# P_EV.net
KiCad netlist of a schematic drawn in Altium Designer
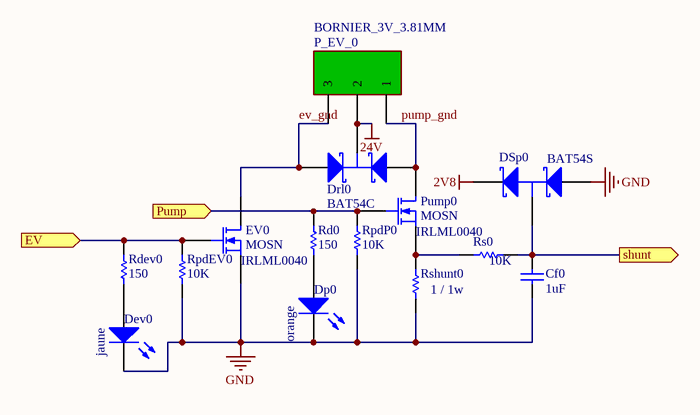
[diagram p0: P+EV.SchDoc]

(export (version "E")
  (design (tool "Eeschema 10.0.6"))
  (components
    (comp (ref "Cf0")
      (value "1uF")
      (footprint "C0805_N")
      (description "Capacitor")
      (fields (field (name "PUBLISHER") "Altium Limited"))
      (libsource (lib "_ROBOT") (part "Condensateur"))
    )
    (comp (ref "Dev0")
      (value "jaune")
      (footprint "LED_0805")
      (description "Typical LED")
      (fields (field (name "PUBLISHER") "Altium Limited"))
      (libsource (lib "_ROBOT") (part "LED"))
    )
    (comp (ref "Dp0")
      (value "orange")
      (footprint "LED_0805")
      (description "Typical LED")
      (fields (field (name "PUBLISHER") "Altium Limited"))
      (libsource (lib "_ROBOT") (part "LED"))
    )
    (comp (ref "Drl0")
      (value "BAT54C")
      (footprint "SOT23-3N")
      (description "DIODE SCHOTTKY DOUBLE")
      (fields (field (name "MANUFACTURER") "ZETEX"))
      (libsource (lib "_ROBOT") (part "Diode Shottky double BAT54C"))
    )
    (comp (ref "DSp0")
      (value "BAT54S")
      (footprint "SOT23-3N")
      (description "DIODE SCHOTTKY DOUBLE")
      (fields (field (name "MANUFACTURER") "ZETEX"))
      (libsource (lib "_ROBOT") (part "Diode Shottky double BAT54S"))
    )
    (comp (ref "EV0")
      (value "MOSN")
      (footprint "SOT23-3N")
      (description "N-Channel MOSFET")
      (fields (field (name "ALTIUM_UNNAMED_1") "IRLML0040") (field (name "PUBLISHER") "Altium Limited"))
      (libsource (lib "_ROBOT") (part "Transistor MOSFET-N"))
    )
    (comp (ref "Pump0")
      (value "MOSN")
      (footprint "SOT23-3N")
      (description "N-Channel MOSFET")
      (fields (field (name "ALTIUM_UNNAMED_1") "IRLML0040") (field (name "PUBLISHER") "Altium Limited"))
      (libsource (lib "_ROBOT") (part "Transistor MOSFET-N"))
    )
    (comp (ref "P_EV_0")
      (value "BORNIER_3V_3.81MM")
      (footprint "BORNIER_3V_3.81MM")
      (libsource (lib "Connecteur") (part "BORNIER_3V_3.81MM"))
    )
    (comp (ref "Rd0")
      (value "150")
      (footprint "R1206_N")
      (description "Resistor")
      (fields (field (name "PUBLISHER") "Altium Limited"))
      (libsource (lib "_ROBOT") (part "Resistor"))
    )
    (comp (ref "Rdev0")
      (value "150")
      (footprint "R1206_N")
      (description "Resistor")
      (fields (field (name "PUBLISHER") "Altium Limited"))
      (libsource (lib "_ROBOT") (part "Resistor"))
    )
    (comp (ref "RpdEV0")
      (value "10K")
      (footprint "R1206_N")
      (description "Resistor")
      (fields (field (name "PUBLISHER") "Altium Limited"))
      (libsource (lib "_ROBOT") (part "Resistor"))
    )
    (comp (ref "RpdP0")
      (value "10K")
      (footprint "R1206_N")
      (description "Resistor")
      (fields (field (name "PUBLISHER") "Altium Limited"))
      (libsource (lib "_ROBOT") (part "Resistor"))
    )
    (comp (ref "Rs0")
      (value "10K")
      (footprint "R1206_N")
      (description "Resistor")
      (fields (field (name "PUBLISHER") "Altium Limited"))
      (libsource (lib "_ROBOT") (part "Resistor"))
    )
    (comp (ref "Rshunt0")
      (value "1 / 1w")
      (footprint "INDUCTANCE_CMS_1812")
      (description "Resistor")
      (fields (field (name "PUBLISHER") "Altium Limited"))
      (libsource (lib "_ROBOT") (part "Resistor"))
    )
  )
  (nets
    (net (code "1") (name "/EV") (class "Default")
      (node (ref "EV0") (pin "1") (pinfunction "G_1") (pintype "passive"))
      (node (ref "Rdev0") (pin "2") (pinfunction "2_2") (pintype "passive"))
      (node (ref "RpdEV0") (pin "2") (pinfunction "2_2") (pintype "passive"))
    )
    (net (code "2") (name "/Pump") (class "Default")
      (node (ref "Pump0") (pin "1") (pinfunction "G_1") (pintype "passive"))
      (node (ref "Rd0") (pin "2") (pinfunction "2_2") (pintype "passive"))
      (node (ref "RpdP0") (pin "2") (pinfunction "2_2") (pintype "passive"))
    )
    (net (code "3") (name "/ev_gnd") (class "Default")
      (node (ref "Drl0") (pin "1") (pinfunction "A1_1") (pintype "passive"))
      (node (ref "EV0") (pin "3") (pinfunction "D_3") (pintype "passive"))
      (node (ref "P_EV_0") (pin "3") (pinfunction "3_3") (pintype "passive"))
    )
    (net (code "4") (name "/pump_gnd") (class "Default")
      (node (ref "Drl0") (pin "2") (pinfunction "A2_2") (pintype "passive"))
      (node (ref "P_EV_0") (pin "1") (pinfunction "1_1") (pintype "passive"))
      (node (ref "Pump0") (pin "3") (pinfunction "D_3") (pintype "passive"))
    )
    (net (code "5") (name "/shunt") (class "Default")
      (node (ref "Cf0") (pin "2") (pinfunction "2_2") (pintype "passive"))
      (node (ref "DSp0") (pin "3") (pinfunction "C_3") (pintype "passive"))
      (node (ref "Rs0") (pin "2") (pinfunction "2_2") (pintype "passive"))
    )
    (net (code "6") (name "2V8") (class "Default")
      (node (ref "DSp0") (pin "2") (pinfunction "K_2") (pintype "passive"))
    )
    (net (code "7") (name "24V") (class "Default")
      (node (ref "Drl0") (pin "3") (pinfunction "K_3") (pintype "passive"))
      (node (ref "P_EV_0") (pin "2") (pinfunction "2_2") (pintype "passive"))
    )
    (net (code "8") (name "GND") (class "Default")
      (node (ref "Cf0") (pin "1") (pinfunction "1_1") (pintype "passive"))
      (node (ref "DSp0") (pin "1") (pinfunction "A_1") (pintype "passive"))
      (node (ref "Dev0") (pin "2") (pinfunction "K_2") (pintype "passive"))
      (node (ref "Dp0") (pin "2") (pinfunction "K_2") (pintype "passive"))
      (node (ref "EV0") (pin "2") (pinfunction "S_2") (pintype "passive"))
      (node (ref "RpdEV0") (pin "1") (pinfunction "1_1") (pintype "passive"))
      (node (ref "RpdP0") (pin "1") (pinfunction "1_1") (pintype "passive"))
      (node (ref "Rshunt0") (pin "1") (pinfunction "1_1") (pintype "passive"))
    )
    (net (code "9") (name "Net-(Dev0-A)") (class "Default")
      (node (ref "Dev0") (pin "1") (pinfunction "A_1") (pintype "passive"))
      (node (ref "Rdev0") (pin "1") (pinfunction "1_1") (pintype "passive"))
    )
    (net (code "10") (name "Net-(Dp0-A)") (class "Default")
      (node (ref "Dp0") (pin "1") (pinfunction "A_1") (pintype "passive"))
      (node (ref "Rd0") (pin "1") (pinfunction "1_1") (pintype "passive"))
    )
    (net (code "11") (name "Net-(Pump0-S)") (class "Default")
      (node (ref "Pump0") (pin "2") (pinfunction "S_2") (pintype "passive"))
      (node (ref "Rs0") (pin "1") (pinfunction "1_1") (pintype "passive"))
      (node (ref "Rshunt0") (pin "2") (pinfunction "2_2") (pintype "passive"))
    )
  )
)
